# DoorLocker.net
KiCad netlist of a schematic drawn in Altium Designer
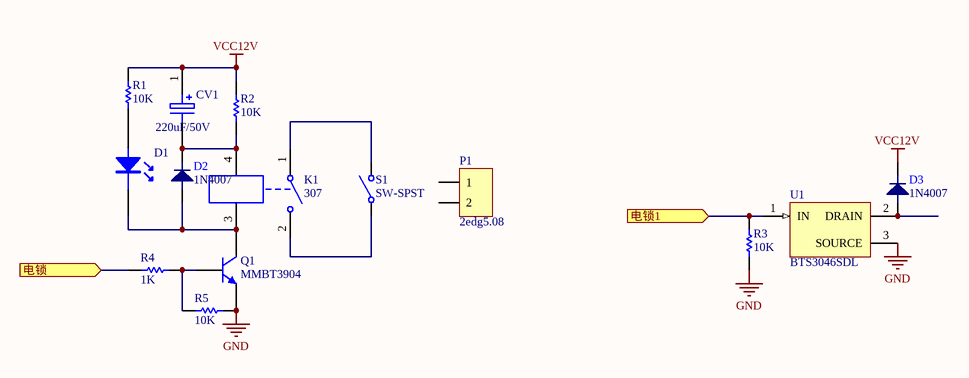
[diagram p0: DoorLocker.SchDoc]

(export (version "E")
  (design (tool "Eeschema 10.0.6"))
  (components
    (comp (ref "CV1")
      (value "220uF/50V")
      (footprint "CAPPR5-10x20/H1.1")
      (description "aluminum electrolytic capacitor")
      (fields (field (name "MANUFACTURER") "Yageo"))
      (libsource (lib "*") (part "ELECTRO1"))
    )
    (comp (ref "D1") (value "~") (footprint "0805-L") (libsource (lib "*") (part "LED")))
    (comp (ref "D2")
      (value "1N4007")
      (footprint "DO-214AC(SMA)")
      (description "1A整流二极管")
      (libsource (lib "mylib") (part "1N4007"))
    )
    (comp (ref "D3")
      (value "1N4007")
      (footprint "DO-214AC(SMA)")
      (description "1A整流二极管")
      (libsource (lib "mylib") (part "1N4007"))
    )
    (comp (ref "K1")
      (value "307")
      (footprint "RELAY-SONGCHUAN")
      (description "继电器")
      (libsource (lib "mylib") (part "JDQ_307"))
    )
    (comp (ref "P1")
      (value "2edg5.08")
      (footprint "2edg5.08_2")
      (description "端子")
      (libsource (lib "mylib") (part "2EDG5.08_2"))
    )
    (comp (ref "Q1")
      (value "MMBT3904")
      (footprint "SOT23_N")
      (description "NPN Switching Transistor")
      (fields (field (name "PUBLISHER") "Altium Limited"))
      (libsource (lib "Philips Discrete BJT - Low Power") (part "MMBT3904"))
    )
    (comp (ref "R1")
      (value "10K")
      (footprint "RESC0805(2012)_M")
      (description "10K 0.125W 1% 0805 (2012 Metric)  SMD")
      (fields (field (name "TOLERANCE") "1 %") (field (name "POWER") "0.125 W"))
      (libsource (lib "Altium Content Vault") (part "CMP-1013-00623-1"))
    )
    (comp (ref "R2")
      (value "10K")
      (footprint "RESC0805(2012)_M")
      (description "10K 0.125W 1% 0805 (2012 Metric)  SMD")
      (fields (field (name "TOLERANCE") "1 %") (field (name "POWER") "0.125 W"))
      (libsource (lib "Altium Content Vault") (part "CMP-1013-00623-1"))
    )
    (comp (ref "R3")
      (value "10K")
      (footprint "RESC0805(2012)_M")
      (description "10K 0.125W 1% 0805 (2012 Metric)  SMD")
      (fields (field (name "TOLERANCE") "1 %") (field (name "POWER") "0.125 W"))
      (libsource (lib "Altium Content Vault") (part "CMP-1013-00623-1"))
    )
    (comp (ref "R4")
      (value "1K")
      (footprint "RESC0805(2012)_M")
      (description "1K 0.125W 1% 0805 (2012 Metric)  SMD")
      (fields (field (name "TOLERANCE") "1 %") (field (name "POWER") "0.125 W"))
      (libsource (lib "Altium Content Vault") (part "CMP-1013-00510-1"))
    )
    (comp (ref "R5")
      (value "10K")
      (footprint "RESC0805(2012)_M")
      (description "10K 0.125W 1% 0805 (2012 Metric)  SMD")
      (fields (field (name "TOLERANCE") "1 %") (field (name "POWER") "0.125 W"))
      (libsource (lib "Altium Content Vault") (part "CMP-1013-00623-1"))
    )
    (comp (ref "S1")
      (value "SW-SPST")
      (footprint "SPST-2")
      (description "Single-Pole, Single-Throw Switch")
      (fields (field (name "PUBLISHER") "Altium Limited"))
      (libsource (lib "Miscellaneous Devices") (part "SW-SPST"))
    )
    (comp (ref "U1")
      (value "BTS3046SDL")
      (footprint "INF-PG-TO252-3-11_M")
      (fields (field (name "MANUFACTURER") "Infineon"))
      (libsource (lib "Altium Content Vault") (part "INF-BTS3XXXSDX-PG-TO252-3-11-2"))
    )
  )
  (nets
    (net (code "1") (name "/电锁") (class "Default")
      (node (ref "R4") (pin "2") (pinfunction "2_2") (pintype "passive"))
    )
    (net (code "2") (name "/电锁1") (class "Default")
      (node (ref "R3") (pin "1") (pinfunction "1_1") (pintype "passive"))
      (node (ref "U1") (pin "1") (pinfunction "IN_1") (pintype "input"))
    )
    (net (code "3") (name "GND") (class "Default")
      (node (ref "Q1") (pin "2") (pinfunction "E_2") (pintype "passive"))
      (node (ref "R3") (pin "2") (pinfunction "2_2") (pintype "passive"))
      (node (ref "R5") (pin "1") (pinfunction "1_1") (pintype "passive"))
      (node (ref "U1") (pin "3") (pinfunction "SOURCE_3") (pintype "power_in"))
    )
    (net (code "4") (name "Net-(CV1-Pad2)") (class "Default")
      (node (ref "CV1") (pin "2") (pinfunction "2_2") (pintype "passive"))
      (node (ref "D2") (pin "2") (pintype "passive"))
      (node (ref "K1") (pin "4") (pinfunction "4_4") (pintype "passive"))
      (node (ref "R2") (pin "2") (pinfunction "2_2") (pintype "passive"))
    )
    (net (code "5") (name "Net-(D1-Pad1)") (class "Default")
      (node (ref "D1") (pin "1") (pinfunction "1_1") (pintype "passive"))
      (node (ref "R1") (pin "2") (pinfunction "2_2") (pintype "passive"))
    )
    (net (code "6") (name "Net-(Q1-B)") (class "Default")
      (node (ref "Q1") (pin "1") (pinfunction "B_1") (pintype "passive"))
      (node (ref "R4") (pin "1") (pinfunction "1_1") (pintype "passive"))
      (node (ref "R5") (pin "2") (pinfunction "2_2") (pintype "passive"))
    )
    (net (code "7") (name "Net-(Q1-C)") (class "Default")
      (node (ref "D1") (pin "2") (pinfunction "2_2") (pintype "passive"))
      (node (ref "D2") (pin "1") (pintype "passive"))
      (node (ref "K1") (pin "3") (pinfunction "3_3") (pintype "passive"))
      (node (ref "Q1") (pin "3") (pinfunction "C_3") (pintype "passive"))
    )
    (net (code "8") (name "Net-(S1-COMMON)") (class "Default")
      (node (ref "K1") (pin "2") (pinfunction "2_2") (pintype "passive"))
      (node (ref "S1") (pin "1") (pinfunction "COMMON_1") (pintype "passive"))
    )
    (net (code "9") (name "Net-(S1-NO)") (class "Default")
      (node (ref "K1") (pin "1") (pinfunction "1_1") (pintype "passive"))
      (node (ref "S1") (pin "2") (pinfunction "NO_2") (pintype "passive"))
    )
    (net (code "10") (name "Net-(U1-DRAIN)") (class "Default")
      (node (ref "D3") (pin "1") (pintype "passive"))
      (node (ref "U1") (pin "2") (pinfunction "DRAIN_2") (pintype "power_in"))
    )
    (net (code "11") (name "VCC12V") (class "Default")
      (node (ref "CV1") (pin "1") (pinfunction "1_1") (pintype "passive"))
      (node (ref "D3") (pin "2") (pintype "passive"))
      (node (ref "R1") (pin "1") (pinfunction "1_1") (pintype "passive"))
      (node (ref "R2") (pin "1") (pinfunction "1_1") (pintype "passive"))
    )
    (net (code "12") (name "unconnected-(P1-Pad1)") (class "Default")
      (node (ref "P1") (pin "1") (pinfunction "1_1") (pintype "passive"))
    )
    (net (code "13") (name "unconnected-(P1-Pad2)") (class "Default")
      (node (ref "P1") (pin "2") (pinfunction "2_2") (pintype "passive"))
    )
  )
)
